# LAN9254_A_P2.net
KiCad netlist of a schematic drawn in Altium Designer
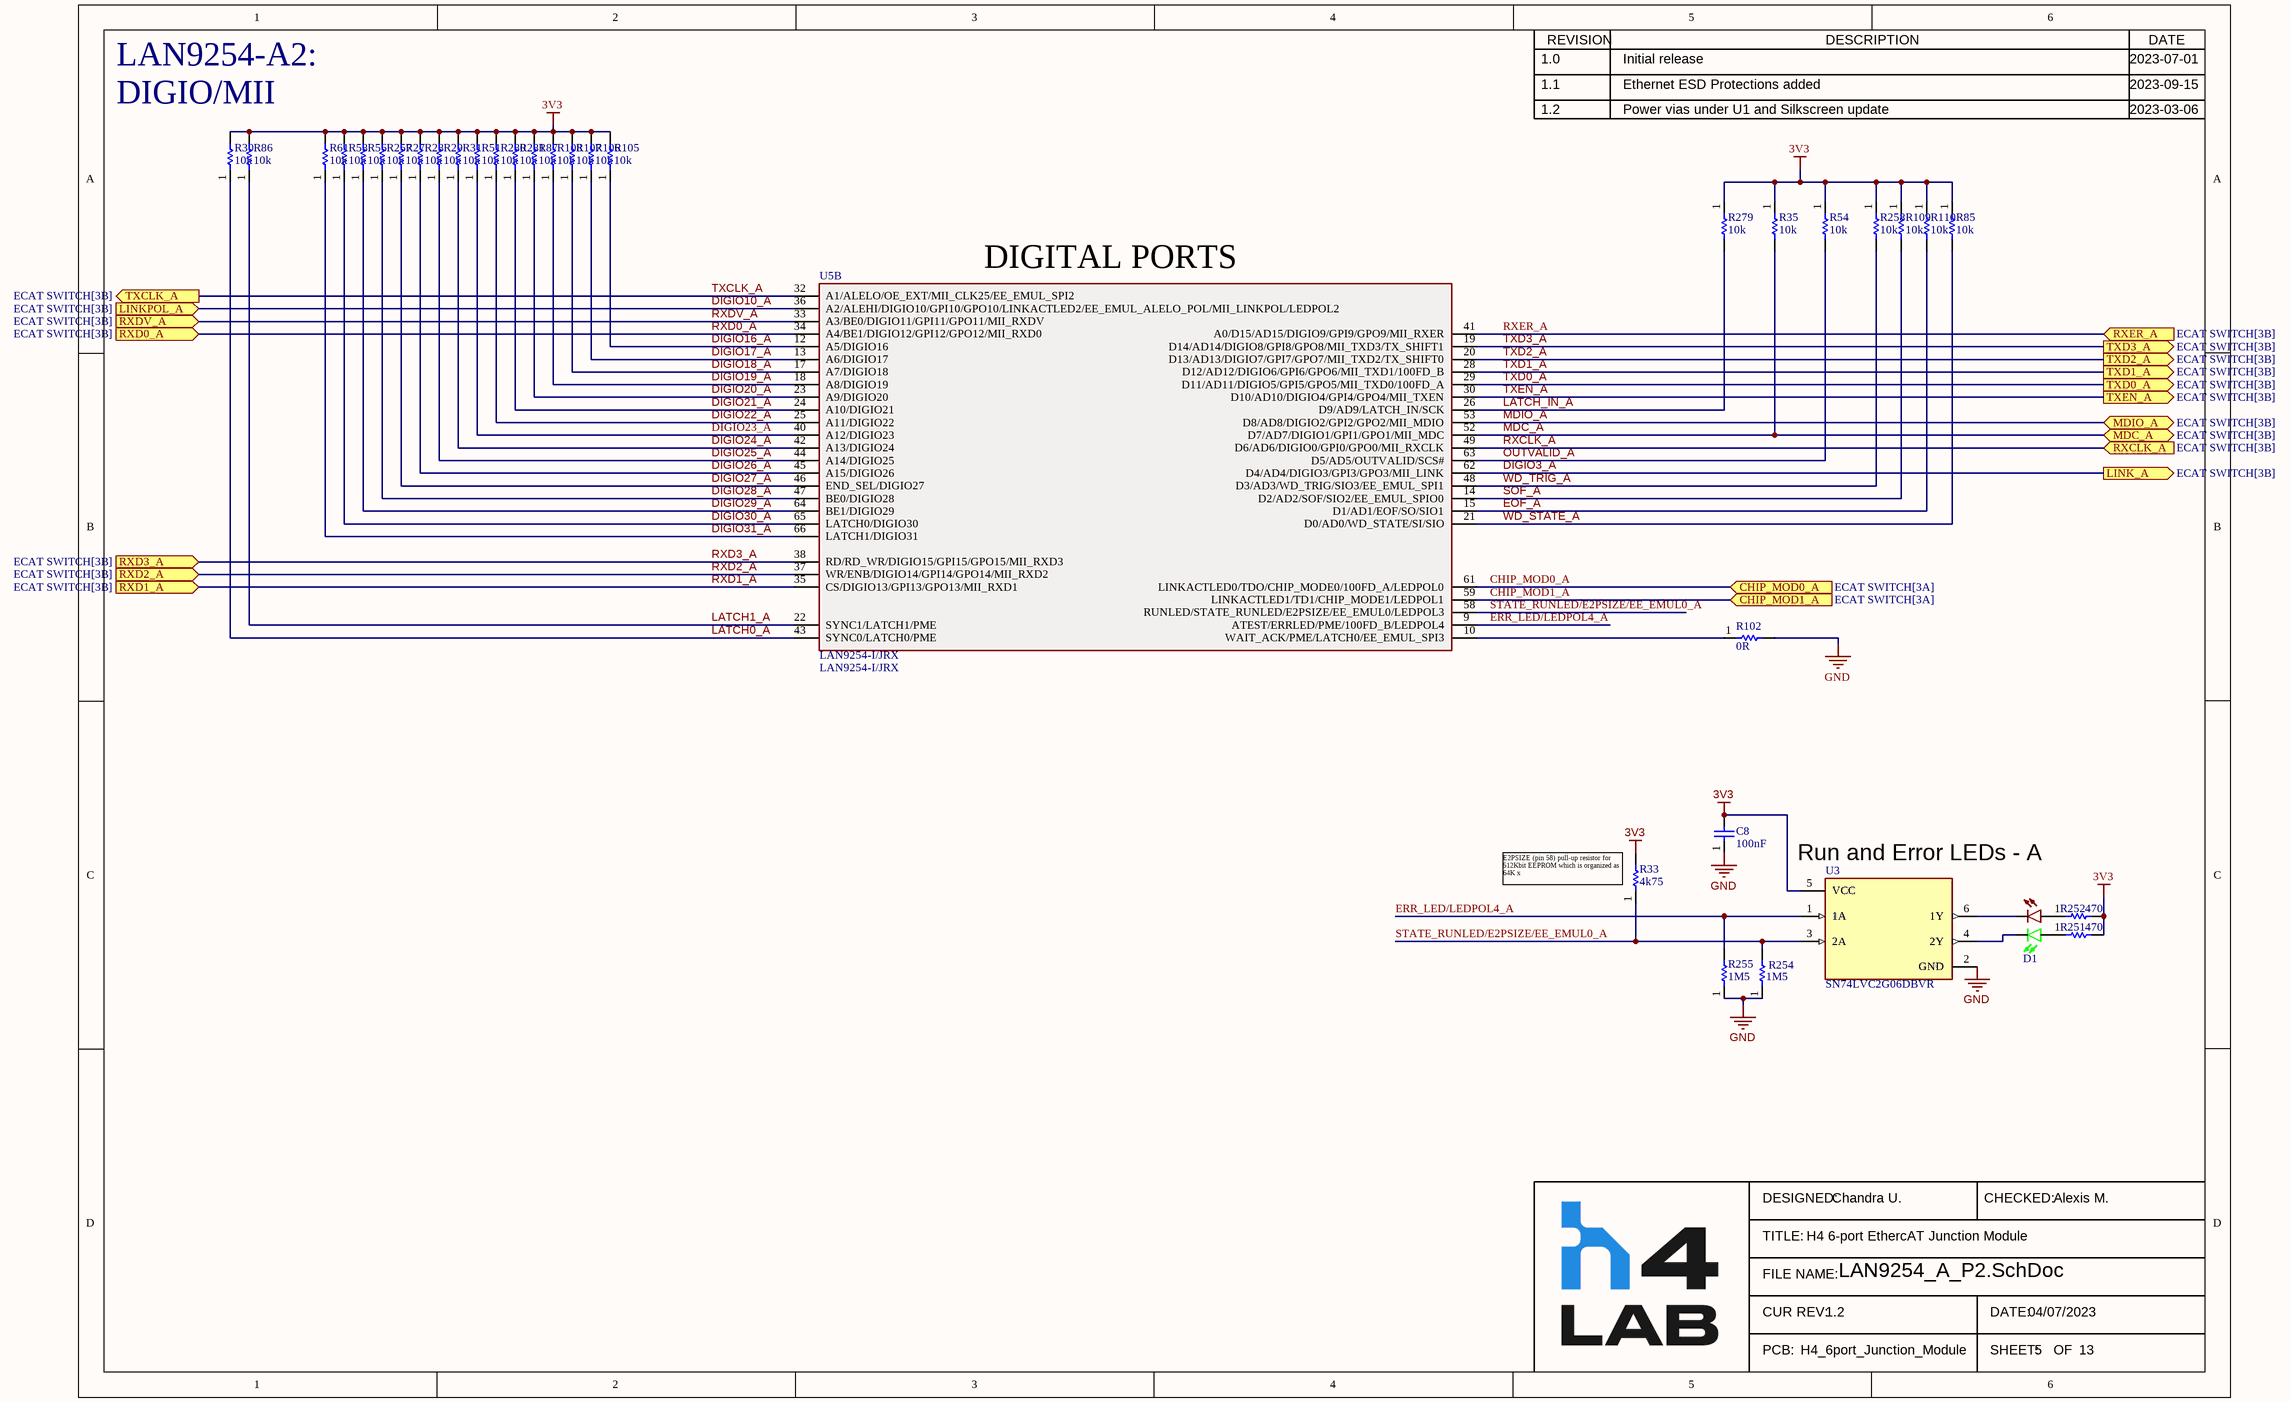
[diagram p0: LAN9254_A_P2.SchDoc]

(export (version "E")
  (design (tool "Eeschema 10.0.6"))
  (components
    (comp (ref "C8")
      (value "100nF")
      (footprint "CAPC1005X03N(0402)")
      (description "CAP CER 0.1UF 16V X7R 0402")
      (fields (field (name "MPN") "GRM155R71C104JA88D") (field (name "TOLERANCE") "5%"))
      (libsource (lib "IHMC_Altium_Lib") (part "100nF_16V_0402_CAP"))
    )
    (comp (ref "D1")
      (value "LTST-C195KGJRKT")
      (footprint "Dual_LED")
      (description "LED GREEN/RED CLEAR CHIP SMD")
      (libsource (lib "IHMC_Altium_Lib") (part "Green/Red_LED"))
    )
    (comp (ref "R27")
      (value "10k")
      (footprint "RESC1005X06N(0402)")
      (description "RES SMD 10K OHM 1% 1/16W 0402")
      (fields (field (name "MPN") "RC0402FR-0710KL") (field (name "TOLERANCE") "1%"))
      (libsource (lib "IHMC_Resistors") (part "10k_1/16W_0402_RES"))
    )
    (comp (ref "R28")
      (value "10k")
      (footprint "RESC1005X06N(0402)")
      (description "RES SMD 10K OHM 1% 1/16W 0402")
      (fields (field (name "MPN") "RC0402FR-0710KL") (field (name "TOLERANCE") "1%"))
      (libsource (lib "IHMC_Resistors") (part "10k_1/16W_0402_RES"))
    )
    (comp (ref "R29")
      (value "10k")
      (footprint "RESC1005X06N(0402)")
      (description "RES SMD 10K OHM 1% 1/16W 0402")
      (fields (field (name "MPN") "RC0402FR-0710KL") (field (name "TOLERANCE") "1%"))
      (libsource (lib "IHMC_Resistors") (part "10k_1/16W_0402_RES"))
    )
    (comp (ref "R30")
      (value "10k")
      (footprint "RESC1005X06N(0402)")
      (description "RES SMD 10K OHM 1% 1/16W 0402")
      (fields (field (name "MPN") "RC0402FR-0710KL") (field (name "TOLERANCE") "1%"))
      (libsource (lib "IHMC_Resistors") (part "10k_1/16W_0402_RES"))
    )
    (comp (ref "R31")
      (value "10k")
      (footprint "RESC1005X06N(0402)")
      (description "RES SMD 10K OHM 1% 1/16W 0402")
      (fields (field (name "MPN") "RC0402FR-0710KL") (field (name "TOLERANCE") "1%"))
      (libsource (lib "IHMC_Resistors") (part "10k_1/16W_0402_RES"))
    )
    (comp (ref "R33")
      (value "4k75")
      (footprint "RESC1005X06N(0402)")
      (description "RES SMD 4.75K OHM 1% 1/16W 0402")
      (fields (field (name "MPN") "RC0402FR-074K75L") (field (name "POWER") "1/16"))
      (libsource (lib "IHMC_Altium_Lib") (part "4k75_1/16_0402_RES"))
    )
    (comp (ref "R35")
      (value "10k")
      (footprint "RESC1005X06N(0402)")
      (description "RES SMD 10K OHM 1% 1/16W 0402")
      (fields (field (name "MPN") "RC0402FR-0710KL") (field (name "TOLERANCE") "1%"))
      (libsource (lib "IHMC_Resistors") (part "10k_1/16W_0402_RES"))
    )
    (comp (ref "R51")
      (value "10k")
      (footprint "RESC1005X06N(0402)")
      (description "RES SMD 10K OHM 1% 1/16W 0402")
      (fields (field (name "MPN") "RC0402FR-0710KL") (field (name "TOLERANCE") "1%"))
      (libsource (lib "IHMC_Resistors") (part "10k_1/16W_0402_RES"))
    )
    (comp (ref "R54")
      (value "10k")
      (footprint "RESC1005X06N(0402)")
      (description "RES SMD 10K OHM 1% 1/16W 0402")
      (fields (field (name "MPN") "RC0402FR-0710KL") (field (name "TOLERANCE") "1%"))
      (libsource (lib "IHMC_Resistors") (part "10k_1/16W_0402_RES"))
    )
    (comp (ref "R56")
      (value "10k")
      (footprint "RESC1005X06N(0402)")
      (description "RES SMD 10K OHM 1% 1/16W 0402")
      (fields (field (name "MPN") "RC0402FR-0710KL") (field (name "TOLERANCE") "1%"))
      (libsource (lib "IHMC_Resistors") (part "10k_1/16W_0402_RES"))
    )
    (comp (ref "R58")
      (value "10k")
      (footprint "RESC1005X06N(0402)")
      (description "RES SMD 10K OHM 1% 1/16W 0402")
      (fields (field (name "MPN") "RC0402FR-0710KL") (field (name "TOLERANCE") "1%"))
      (libsource (lib "IHMC_Resistors") (part "10k_1/16W_0402_RES"))
    )
    (comp (ref "R61")
      (value "10k")
      (footprint "RESC1005X06N(0402)")
      (description "RES SMD 10K OHM 1% 1/16W 0402")
      (fields (field (name "MPN") "RC0402FR-0710KL") (field (name "TOLERANCE") "1%"))
      (libsource (lib "IHMC_Resistors") (part "10k_1/16W_0402_RES"))
    )
    (comp (ref "R85")
      (value "10k")
      (footprint "RESC1005X06N(0402)")
      (description "RES SMD 10K OHM 1% 1/16W 0402")
      (fields (field (name "MPN") "RC0402FR-0710KL") (field (name "TOLERANCE") "1%"))
      (libsource (lib "IHMC_Resistors") (part "10k_1/16W_0402_RES"))
    )
    (comp (ref "R86")
      (value "10k")
      (footprint "RESC1005X06N(0402)")
      (description "RES SMD 10K OHM 1% 1/16W 0402")
      (fields (field (name "MPN") "RC0402FR-0710KL") (field (name "TOLERANCE") "1%"))
      (libsource (lib "IHMC_Resistors") (part "10k_1/16W_0402_RES"))
    )
    (comp (ref "R87")
      (value "10k")
      (footprint "RESC1005X06N(0402)")
      (description "RES SMD 10K OHM 1% 1/16W 0402")
      (fields (field (name "MPN") "RC0402FR-0710KL") (field (name "TOLERANCE") "1%"))
      (libsource (lib "IHMC_Resistors") (part "10k_1/16W_0402_RES"))
    )
    (comp (ref "R102")
      (value "0R")
      (footprint "0402")
      (fields
        (field (name "MANUFACTURER") "Vishay Dale")
        (field (name "MANUFACTURER PART NUMBER") "RCS04020000Z0ED")
      )
      (libsource (lib "IHMC_Altium_Lib") (part "0R_1/5W_0402_RCS04020000Z0ED_RES"))
    )
    (comp (ref "R105")
      (value "10k")
      (footprint "RESC1005X06N(0402)")
      (description "RES SMD 10K OHM 1% 1/16W 0402")
      (fields (field (name "MPN") "RC0402FR-0710KL") (field (name "TOLERANCE") "1%"))
      (libsource (lib "IHMC_Resistors") (part "10k_1/16W_0402_RES"))
    )
    (comp (ref "R106")
      (value "10k")
      (footprint "RESC1005X06N(0402)")
      (description "RES SMD 10K OHM 1% 1/16W 0402")
      (fields (field (name "MPN") "RC0402FR-0710KL") (field (name "TOLERANCE") "1%"))
      (libsource (lib "IHMC_Resistors") (part "10k_1/16W_0402_RES"))
    )
    (comp (ref "R107")
      (value "10k")
      (footprint "RESC1005X06N(0402)")
      (description "RES SMD 10K OHM 1% 1/16W 0402")
      (fields (field (name "MPN") "RC0402FR-0710KL") (field (name "TOLERANCE") "1%"))
      (libsource (lib "IHMC_Resistors") (part "10k_1/16W_0402_RES"))
    )
    (comp (ref "R108")
      (value "10k")
      (footprint "RESC1005X06N(0402)")
      (description "RES SMD 10K OHM 1% 1/16W 0402")
      (fields (field (name "MPN") "RC0402FR-0710KL") (field (name "TOLERANCE") "1%"))
      (libsource (lib "IHMC_Resistors") (part "10k_1/16W_0402_RES"))
    )
    (comp (ref "R109")
      (value "10k")
      (footprint "RESC1005X06N(0402)")
      (description "RES SMD 10K OHM 1% 1/16W 0402")
      (fields (field (name "MPN") "RC0402FR-0710KL") (field (name "TOLERANCE") "1%"))
      (libsource (lib "IHMC_Resistors") (part "10k_1/16W_0402_RES"))
    )
    (comp (ref "R110")
      (value "10k")
      (footprint "RESC1005X06N(0402)")
      (description "RES SMD 10K OHM 1% 1/16W 0402")
      (fields (field (name "MPN") "RC0402FR-0710KL") (field (name "TOLERANCE") "1%"))
      (libsource (lib "IHMC_Resistors") (part "10k_1/16W_0402_RES"))
    )
    (comp (ref "R251")
      (value "470")
      (footprint "0402")
      (description "Vishay CRCW Series Thick Film Resistor 0402 Case 470 5% 0.063W 200ppm/K")
      (fields
        (field (name "MANUFACTURER") "Vishay Dale")
        (field (name "MANUFACTURER PART NUMBER") "CRCW0402470RJNED")
      )
      (libsource (lib "IHMC_Altium_Lib") (part "470_1/10W_0402_CRCW0402470RJNED"))
    )
    (comp (ref "R252")
      (value "470")
      (footprint "0402")
      (description "Vishay CRCW Series Thick Film Resistor 0402 Case 470 5% 0.063W 200ppm/K")
      (fields
        (field (name "MANUFACTURER") "Vishay Dale")
        (field (name "MANUFACTURER PART NUMBER") "CRCW0402470RJNED")
      )
      (libsource (lib "IHMC_Altium_Lib") (part "470_1/10W_0402_CRCW0402470RJNED"))
    )
    (comp (ref "R254")
      (value "1M5")
      (footprint "0402")
      (description "RES SMD 1.5M OHM 5% 1/16W 0402")
      (fields
        (field (name "MANUFACTURER") "Vishay Dale")
        (field (name "MANUFACTURER PART NUMBER") "CRCW04021M50JNED")
      )
      (libsource (lib "IHMC_Altium_Lib") (part "1M5_1/16W_0402_CRCW04021M50JNED_RES"))
    )
    (comp (ref "R255")
      (value "1M5")
      (footprint "0402")
      (description "RES SMD 1.5M OHM 5% 1/16W 0402")
      (fields
        (field (name "MANUFACTURER") "Vishay Dale")
        (field (name "MANUFACTURER PART NUMBER") "CRCW04021M50JNED")
      )
      (libsource (lib "IHMC_Altium_Lib") (part "1M5_1/16W_0402_CRCW04021M50JNED_RES"))
    )
    (comp (ref "R257")
      (value "10k")
      (footprint "RESC1005X06N(0402)")
      (description "RES SMD 10K OHM 1% 1/16W 0402")
      (fields (field (name "MPN") "RC0402FR-0710KL") (field (name "TOLERANCE") "1%"))
      (libsource (lib "IHMC_Resistors") (part "10k_1/16W_0402_RES"))
    )
    (comp (ref "R258")
      (value "10k")
      (footprint "RESC1005X06N(0402)")
      (description "RES SMD 10K OHM 1% 1/16W 0402")
      (fields (field (name "MPN") "RC0402FR-0710KL") (field (name "TOLERANCE") "1%"))
      (libsource (lib "IHMC_Resistors") (part "10k_1/16W_0402_RES"))
    )
    (comp (ref "R279")
      (value "10k")
      (footprint "RESC1005X06N(0402)")
      (description "RES SMD 10K OHM 1% 1/16W 0402")
      (fields (field (name "MPN") "RC0402FR-0710KL") (field (name "TOLERANCE") "1%"))
      (libsource (lib "IHMC_Resistors") (part "10k_1/16W_0402_RES"))
    )
    (comp (ref "R280")
      (value "10k")
      (footprint "RESC1005X06N(0402)")
      (description "RES SMD 10K OHM 1% 1/16W 0402")
      (fields (field (name "MPN") "RC0402FR-0710KL") (field (name "TOLERANCE") "1%"))
      (libsource (lib "IHMC_Resistors") (part "10k_1/16W_0402_RES"))
    )
    (comp (ref "R281")
      (value "10k")
      (footprint "RESC1005X06N(0402)")
      (description "RES SMD 10K OHM 1% 1/16W 0402")
      (fields (field (name "MPN") "RC0402FR-0710KL") (field (name "TOLERANCE") "1%"))
      (libsource (lib "IHMC_Resistors") (part "10k_1/16W_0402_RES"))
    )
    (comp (ref "U3")
      (value "SN74LVC2G06DBVR")
      (footprint "FP-DBV0006A-IPC_C")
      (description "Buffer/Driver 2-CH Inverting Open Drain CMOS 6-Pin SOT-23 T/R")
      (fields (field (name "MANUFACTURER") "Texas Instruments"))
      (libsource (lib "IHMC_Altium_Lib") (part "BUF_dual_SN74LVC2G06DBVR"))
    )
    (comp (ref "U5")
      (value "LAN9254-I/JRX")
      (footprint "QFP50P1400X1400X120-81N")
      (description "2/3-PORT Ethercat Slave Controller With 32 Digios With Integrated Ethernet Phys")
      (fields (field (name "MANUFACTURER") "Microchip"))
      (libsource (lib "IHMC_Ethernet") (part "LAN9254-I/JRX"))
    )
  )
  (nets
    (net (code "1") (name "/CHIP_MOD0_A") (class "Default")
      (node (ref "U5") (pin "61") (pinfunction "LINKACTLED0/TDO/CHIP_MODE0/100FD_A/LEDPOL0_61") (pintype "passive"))
    )
    (net (code "2") (name "/CHIP_MOD1_A") (class "Default")
      (node (ref "U5") (pin "59") (pinfunction "LINKACTLED1/TD1/CHIP_MODE1/LEDPOL1_59") (pintype "passive"))
    )
    (net (code "3") (name "/DIGIO3_A") (class "Default")
      (node (ref "U5") (pin "62") (pinfunction "D4/AD4/DIGIO3/GPI3/GPO3/MII_LINK_62") (pintype "passive"))
    )
    (net (code "4") (name "/DIGIO10_A") (class "Default")
      (node (ref "U5") (pin "36") (pinfunction "A2/ALEHI/DIGIO10/GPI10/GPO10/LINKACTLED2/EE_EMUL_ALELO_POL/MII_LINKPOL/LEDPOL2_36") (pintype "passive"))
    )
    (net (code "5") (name "/DIGIO16_A") (class "Default")
      (node (ref "R105") (pin "1") (pinfunction "1_1") (pintype "passive"))
      (node (ref "U5") (pin "12") (pinfunction "A5/DIGIO16_12") (pintype "passive"))
    )
    (net (code "6") (name "/DIGIO17_A") (class "Default")
      (node (ref "R106") (pin "1") (pinfunction "1_1") (pintype "passive"))
      (node (ref "U5") (pin "13") (pinfunction "A6/DIGIO17_13") (pintype "passive"))
    )
    (net (code "7") (name "/DIGIO18_A") (class "Default")
      (node (ref "R107") (pin "1") (pinfunction "1_1") (pintype "passive"))
      (node (ref "U5") (pin "17") (pinfunction "A7/DIGIO18_17") (pintype "passive"))
    )
    (net (code "8") (name "/DIGIO19_A") (class "Default")
      (node (ref "R108") (pin "1") (pinfunction "1_1") (pintype "passive"))
      (node (ref "U5") (pin "18") (pinfunction "A8/DIGIO19_18") (pintype "passive"))
    )
    (net (code "9") (name "/DIGIO20_A") (class "Default")
      (node (ref "R87") (pin "1") (pinfunction "1_1") (pintype "passive"))
      (node (ref "U5") (pin "23") (pinfunction "A9/DIGIO20_23") (pintype "passive"))
    )
    (net (code "10") (name "/DIGIO21_A") (class "Default")
      (node (ref "R281") (pin "1") (pinfunction "1_1") (pintype "passive"))
      (node (ref "U5") (pin "24") (pinfunction "A10/DIGIO21_24") (pintype "passive"))
    )
    (net (code "11") (name "/DIGIO22_A") (class "Default")
      (node (ref "R280") (pin "1") (pinfunction "1_1") (pintype "passive"))
      (node (ref "U5") (pin "25") (pinfunction "A11/DIGIO22_25") (pintype "passive"))
    )
    (net (code "12") (name "/DIGIO23_A") (class "Default")
      (node (ref "R51") (pin "1") (pinfunction "1_1") (pintype "passive"))
      (node (ref "U5") (pin "40") (pinfunction "A12/DIGIO23_40") (pintype "passive"))
    )
    (net (code "13") (name "/DIGIO24_A") (class "Default")
      (node (ref "R31") (pin "1") (pinfunction "1_1") (pintype "passive"))
      (node (ref "U5") (pin "42") (pinfunction "A13/DIGIO24_42") (pintype "passive"))
    )
    (net (code "14") (name "/DIGIO25_A") (class "Default")
      (node (ref "R29") (pin "1") (pinfunction "1_1") (pintype "passive"))
      (node (ref "U5") (pin "44") (pinfunction "A14/DIGIO25_44") (pintype "passive"))
    )
    (net (code "15") (name "/DIGIO26_A") (class "Default")
      (node (ref "R28") (pin "1") (pinfunction "1_1") (pintype "passive"))
      (node (ref "U5") (pin "45") (pinfunction "A15/DIGIO26_45") (pintype "passive"))
    )
    (net (code "16") (name "/DIGIO27_A") (class "Default")
      (node (ref "R27") (pin "1") (pinfunction "1_1") (pintype "passive"))
      (node (ref "U5") (pin "46") (pinfunction "END_SEL/DIGIO27_46") (pintype "passive"))
    )
    (net (code "17") (name "/DIGIO28_A") (class "Default")
      (node (ref "R257") (pin "1") (pinfunction "1_1") (pintype "passive"))
      (node (ref "U5") (pin "47") (pinfunction "BE0/DIGIO28_47") (pintype "passive"))
    )
    (net (code "18") (name "/DIGIO29_A") (class "Default")
      (node (ref "R56") (pin "1") (pinfunction "1_1") (pintype "passive"))
      (node (ref "U5") (pin "64") (pinfunction "BE1/DIGIO29_64") (pintype "passive"))
    )
    (net (code "19") (name "/DIGIO30_A") (class "Default")
      (node (ref "R58") (pin "1") (pinfunction "1_1") (pintype "passive"))
      (node (ref "U5") (pin "65") (pinfunction "LATCH0/DIGIO30_65") (pintype "passive"))
    )
    (net (code "20") (name "/DIGIO31_A") (class "Default")
      (node (ref "R61") (pin "1") (pinfunction "1_1") (pintype "passive"))
      (node (ref "U5") (pin "66") (pinfunction "LATCH1/DIGIO31_66") (pintype "passive"))
    )
    (net (code "21") (name "/EOF_A") (class "Default")
      (node (ref "R110") (pin "2") (pinfunction "2_2") (pintype "passive"))
      (node (ref "U5") (pin "15") (pinfunction "D1/AD1/EOF/SO/SIO1_15") (pintype "passive"))
    )
    (net (code "22") (name "/ERR_LED{slash}LEDPOL4_A") (class "Default")
      (node (ref "R255") (pin "2") (pinfunction "2_2") (pintype "passive"))
      (node (ref "U3") (pin "1") (pinfunction "1A_1") (pintype "input"))
      (node (ref "U5") (pin "9") (pinfunction "ATEST/ERRLED/PME/100FD_B/LEDPOL4_9") (pintype "passive"))
    )
    (net (code "23") (name "/LATCH0_A") (class "Default")
      (node (ref "R30") (pin "1") (pinfunction "1_1") (pintype "passive"))
      (node (ref "U5") (pin "43") (pinfunction "SYNC0/LATCH0/PME_43") (pintype "passive"))
    )
    (net (code "24") (name "/LATCH1_A") (class "Default")
      (node (ref "R86") (pin "1") (pinfunction "1_1") (pintype "passive"))
      (node (ref "U5") (pin "22") (pinfunction "SYNC1/LATCH1/PME_22") (pintype "passive"))
    )
    (net (code "25") (name "/LATCH_IN_A") (class "Default")
      (node (ref "R279") (pin "2") (pinfunction "2_2") (pintype "passive"))
      (node (ref "U5") (pin "26") (pinfunction "D9/AD9/LATCH_IN/SCK_26") (pintype "passive"))
    )
    (net (code "26") (name "/MDC_A") (class "Default")
      (node (ref "R35") (pin "2") (pinfunction "2_2") (pintype "passive"))
      (node (ref "U5") (pin "52") (pinfunction "D7/AD7/DIGIO1/GPI1/GPO1/MII_MDC_52") (pintype "passive"))
    )
    (net (code "27") (name "/MDIO_A") (class "Default")
      (node (ref "U5") (pin "53") (pinfunction "D8/AD8/DIGIO2/GPI2/GPO2/MII_MDIO_53") (pintype "passive"))
    )
    (net (code "28") (name "/OUTVALID_A") (class "Default")
      (node (ref "R54") (pin "2") (pinfunction "2_2") (pintype "passive"))
      (node (ref "U5") (pin "63") (pinfunction "D5/AD5/OUTVALID/SCS#_63") (pintype "passive"))
    )
    (net (code "29") (name "/RXCLK_A") (class "Default")
      (node (ref "U5") (pin "49") (pinfunction "D6/AD6/DIGIO0/GPI0/GPO0/MII_RXCLK_49") (pintype "passive"))
    )
    (net (code "30") (name "/RXD0_A") (class "Default")
      (node (ref "U5") (pin "34") (pinfunction "A4/BE1/DIGIO12/GPI12/GPO12/MII_RXD0_34") (pintype "passive"))
    )
    (net (code "31") (name "/RXD1_A") (class "Default")
      (node (ref "U5") (pin "35") (pinfunction "CS/DIGIO13/GPI13/GPO13/MII_RXD1_35") (pintype "passive"))
    )
    (net (code "32") (name "/RXD2_A") (class "Default")
      (node (ref "U5") (pin "37") (pinfunction "WR/ENB/DIGIO14/GPI14/GPO14/MII_RXD2_37") (pintype "passive"))
    )
    (net (code "33") (name "/RXD3_A") (class "Default")
      (node (ref "U5") (pin "38") (pinfunction "RD/RD_WR/DIGIO15/GPI15/GPO15/MII_RXD3_38") (pintype "passive"))
    )
    (net (code "34") (name "/RXDV_A") (class "Default")
      (node (ref "U5") (pin "33") (pinfunction "A3/BE0/DIGIO11/GPI11/GPO11/MII_RXDV_33") (pintype "passive"))
    )
    (net (code "35") (name "/RXER_A") (class "Default")
      (node (ref "U5") (pin "41") (pinfunction "A0/D15/AD15/DIGIO9/GPI9/GPO9/MII_RXER_41") (pintype "passive"))
    )
    (net (code "36") (name "/SOF_A") (class "Default")
      (node (ref "R109") (pin "2") (pinfunction "2_2") (pintype "passive"))
      (node (ref "U5") (pin "14") (pinfunction "D2/AD2/SOF/SIO2/EE_EMUL_SPIO0_14") (pintype "passive"))
    )
    (net (code "37") (name "/STATE_RUNLED{slash}E2PSIZE{slash}EE_EMUL0_A") (class "Default")
      (node (ref "R254") (pin "2") (pinfunction "2_2") (pintype "passive"))
      (node (ref "R33") (pin "1") (pinfunction "1_1") (pintype "passive"))
      (node (ref "U3") (pin "3") (pinfunction "2A_3") (pintype "input"))
      (node (ref "U5") (pin "58") (pinfunction "RUNLED/STATE_RUNLED/E2PSIZE/EE_EMUL0/LEDPOL3_58") (pintype "passive"))
    )
    (net (code "38") (name "/TXCLK_A") (class "Default")
      (node (ref "U5") (pin "32") (pinfunction "A1/ALELO/OE_EXT/MII_CLK25/EE_EMUL_SPI2_32") (pintype "passive"))
    )
    (net (code "39") (name "/TXD0_A") (class "Default")
      (node (ref "U5") (pin "29") (pinfunction "D11/AD11/DIGIO5/GPI5/GPO5/MII_TXD0/100FD_A_29") (pintype "passive"))
    )
    (net (code "40") (name "/TXD1_A") (class "Default")
      (node (ref "U5") (pin "28") (pinfunction "D12/AD12/DIGIO6/GPI6/GPO6/MII_TXD1/100FD_B_28") (pintype "passive"))
    )
    (net (code "41") (name "/TXD2_A") (class "Default")
      (node (ref "U5") (pin "20") (pinfunction "D13/AD13/DIGIO7/GPI7/GPO7/MII_TXD2/TX_SHIFT0_20") (pintype "passive"))
    )
    (net (code "42") (name "/TXD3_A") (class "Default")
      (node (ref "U5") (pin "19") (pinfunction "D14/AD14/DIGIO8/GPI8/GPO8/MII_TXD3/TX_SHIFT1_19") (pintype "passive"))
    )
    (net (code "43") (name "/TXEN_A") (class "Default")
      (node (ref "U5") (pin "30") (pinfunction "D10/AD10/DIGIO4/GPI4/GPO4/MII_TXEN_30") (pintype "passive"))
    )
    (net (code "44") (name "/WD_STATE_A") (class "Default")
      (node (ref "R85") (pin "2") (pinfunction "2_2") (pintype "passive"))
      (node (ref "U5") (pin "21") (pinfunction "D0/AD0/WD_STATE/SI/SIO_21") (pintype "passive"))
    )
    (net (code "45") (name "/WD_TRIG_A") (class "Default")
      (node (ref "R258") (pin "2") (pinfunction "2_2") (pintype "passive"))
      (node (ref "U5") (pin "48") (pinfunction "D3/AD3/WD_TRIG/SIO3/EE_EMUL_SPI1_48") (pintype "passive"))
    )
    (net (code "46") (name "3V3") (class "Default")
      (node (ref "C8") (pin "2") (pinfunction "2_2") (pintype "passive"))
      (node (ref "R105") (pin "2") (pinfunction "2_2") (pintype "passive"))
      (node (ref "R106") (pin "2") (pinfunction "2_2") (pintype "passive"))
      (node (ref "R107") (pin "2") (pinfunction "2_2") (pintype "passive"))
      (node (ref "R108") (pin "2") (pinfunction "2_2") (pintype "passive"))
      (node (ref "R109") (pin "1") (pinfunction "1_1") (pintype "passive"))
      (node (ref "R110") (pin "1") (pinfunction "1_1") (pintype "passive"))
      (node (ref "R251") (pin "2") (pinfunction "2_2") (pintype "passive"))
      (node (ref "R252") (pin "2") (pinfunction "2_2") (pintype "passive"))
      (node (ref "R257") (pin "2") (pinfunction "2_2") (pintype "passive"))
      (node (ref "R258") (pin "1") (pinfunction "1_1") (pintype "passive"))
      (node (ref "R27") (pin "2") (pinfunction "2_2") (pintype "passive"))
      (node (ref "R279") (pin "1") (pinfunction "1_1") (pintype "passive"))
      (node (ref "R28") (pin "2") (pinfunction "2_2") (pintype "passive"))
      (node (ref "R280") (pin "2") (pinfunction "2_2") (pintype "passive"))
      (node (ref "R281") (pin "2") (pinfunction "2_2") (pintype "passive"))
      (node (ref "R29") (pin "2") (pinfunction "2_2") (pintype "passive"))
      (node (ref "R30") (pin "2") (pinfunction "2_2") (pintype "passive"))
      (node (ref "R31") (pin "2") (pinfunction "2_2") (pintype "passive"))
      (node (ref "R33") (pin "2") (pinfunction "2_2") (pintype "passive"))
      (node (ref "R35") (pin "1") (pinfunction "1_1") (pintype "passive"))
      (node (ref "R51") (pin "2") (pinfunction "2_2") (pintype "passive"))
      (node (ref "R54") (pin "1") (pinfunction "1_1") (pintype "passive"))
      (node (ref "R56") (pin "2") (pinfunction "2_2") (pintype "passive"))
      (node (ref "R58") (pin "2") (pinfunction "2_2") (pintype "passive"))
      (node (ref "R61") (pin "2") (pinfunction "2_2") (pintype "passive"))
      (node (ref "R85") (pin "1") (pinfunction "1_1") (pintype "passive"))
      (node (ref "R86") (pin "2") (pinfunction "2_2") (pintype "passive"))
      (node (ref "R87") (pin "2") (pinfunction "2_2") (pintype "passive"))
      (node (ref "U3") (pin "5") (pinfunction "VCC_5") (pintype "power_in"))
    )
    (net (code "47") (name "GND") (class "Default")
      (node (ref "C8") (pin "1") (pinfunction "1_1") (pintype "passive"))
      (node (ref "R102") (pin "2") (pinfunction "2_2") (pintype "passive"))
      (node (ref "R254") (pin "1") (pinfunction "1_1") (pintype "passive"))
      (node (ref "R255") (pin "1") (pinfunction "1_1") (pintype "passive"))
      (node (ref "U3") (pin "2") (pinfunction "GND_2") (pintype "power_in"))
    )
    (net (code "48") (name "Net-(D1-Pad1)") (class "Default")
      (node (ref "D1") (pin "1") (pinfunction "1_1") (pintype "passive"))
      (node (ref "R251") (pin "1") (pinfunction "1_1") (pintype "passive"))
    )
    (net (code "49") (name "Net-(D1-Pad2)") (class "Default")
      (node (ref "D1") (pin "2") (pinfunction "2_2") (pintype "passive"))
      (node (ref "R252") (pin "1") (pinfunction "1_1") (pintype "passive"))
    )
    (net (code "50") (name "Net-(U3-1Y)") (class "Default")
      (node (ref "D1") (pin "4") (pinfunction "4_4") (pintype "passive"))
      (node (ref "U3") (pin "6") (pinfunction "1Y_6") (pintype "output"))
    )
    (net (code "51") (name "Net-(U3-2Y)") (class "Default")
      (node (ref "D1") (pin "3") (pinfunction "3_3") (pintype "passive"))
      (node (ref "U3") (pin "4") (pinfunction "2Y_4") (pintype "output"))
    )
    (net (code "52") (name "Net-(U5B-WAIT_ACK{slash}PME{slash}LATCH0{slash}EE_EMUL_SPI3)") (class "Default")
      (node (ref "R102") (pin "1") (pinfunction "1_1") (pintype "passive"))
      (node (ref "U5") (pin "10") (pinfunction "WAIT_ACK/PME/LATCH0/EE_EMUL_SPI3_10") (pintype "passive"))
    )
  )
)
